# ProPrj___2026-06-05.net
KiCad netlist of a schematic drawn in EasyEDA Pro
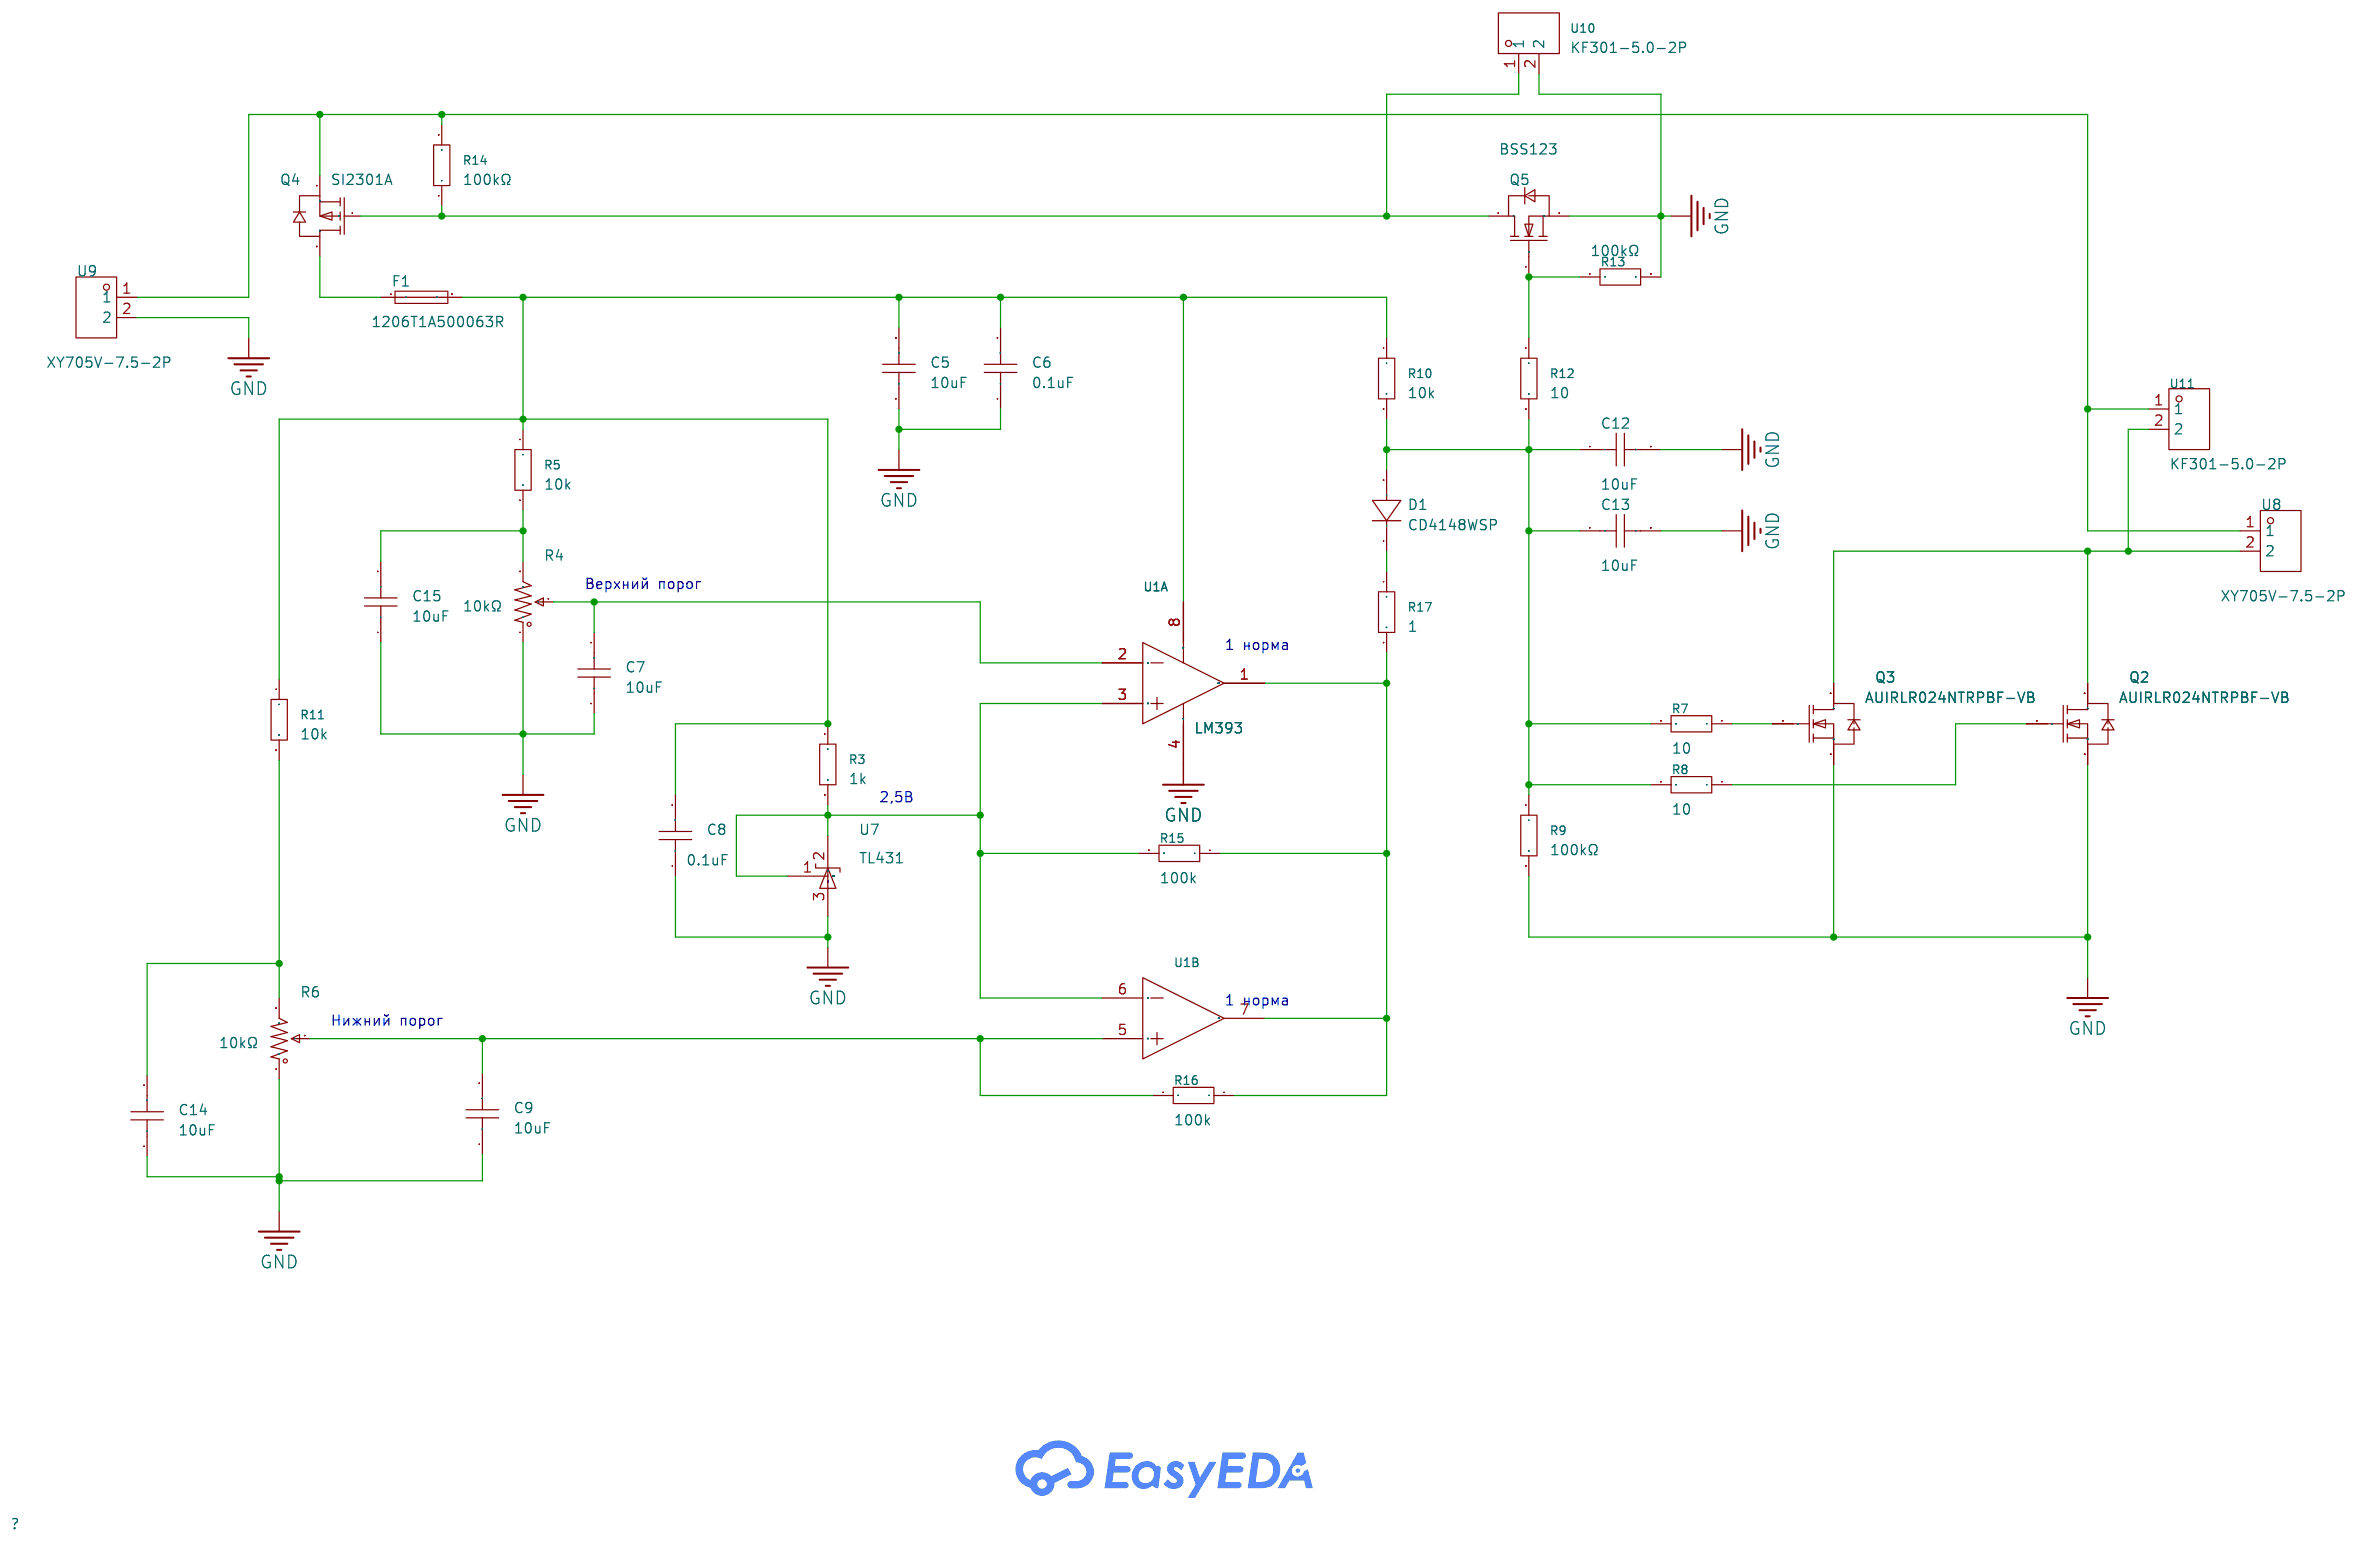
[diagram p0: schematic sheet]

(export (version "E")
  (design (tool "Eeschema 10.0.6"))
  (components
    (comp (ref "C5")
      (value "10uF")
      (footprint "easyedapro:C1206")
      (description "Capacitance:10uF Tolerance:±10% Tolerance:±10% Voltage Rating:50V Temperature Coefficient:X7R")
      (fields (field (name "Manufacturer Part") "1206B106K500NT") (field (name "Manufacturer") "FH(风华)"))
      (libsource (lib "easyedapro") (part "1206B106K500NT"))
    )
    (comp (ref "C6")
      (value "0.1uF")
      (footprint "easyedapro:C1206")
      (description "Capacitance:10uF Tolerance:±10% Tolerance:±10% Voltage Rating:50V Temperature Coefficient:X7R")
      (fields (field (name "Manufacturer Part") "1206B106K500NT") (field (name "Manufacturer") "FH(风华)"))
      (libsource (lib "easyedapro") (part "1206B106K500NT"))
    )
    (comp (ref "C7")
      (value "10uF")
      (footprint "easyedapro:C1206")
      (description "Capacitance:10uF Tolerance:±10% Tolerance:±10% Voltage Rating:50V Temperature Coefficient:X7R")
      (fields (field (name "Manufacturer Part") "1206B106K500NT") (field (name "Manufacturer") "FH(风华)"))
      (libsource (lib "easyedapro") (part "1206B106K500NT"))
    )
    (comp (ref "C8")
      (value "0.1uF")
      (footprint "easyedapro:C1206")
      (description "Capacitance:10uF Tolerance:±10% Tolerance:±10% Voltage Rating:50V Temperature Coefficient:X7R")
      (fields (field (name "Manufacturer Part") "1206B106K500NT") (field (name "Manufacturer") "FH(风华)"))
      (libsource (lib "easyedapro") (part "1206B106K500NT"))
    )
    (comp (ref "C9")
      (value "10uF")
      (footprint "easyedapro:C1206")
      (description "Capacitance:10uF Tolerance:±10% Tolerance:±10% Voltage Rating:50V Temperature Coefficient:X7R")
      (fields (field (name "Manufacturer Part") "1206B106K500NT") (field (name "Manufacturer") "FH(风华)"))
      (libsource (lib "easyedapro") (part "1206B106K500NT"))
    )
    (comp (ref "C12")
      (value "10uF")
      (footprint "easyedapro:C0805")
      (fields (field (name "Manufacturer Part") "C1206X106K025T") (field (name "Manufacturer") "IHHEC(禾伸堂)"))
      (libsource (lib "easyedapro") (part "V106K0805X5R250NHP"))
    )
    (comp (ref "C13")
      (value "10uF")
      (footprint "easyedapro:C0805")
      (fields (field (name "Manufacturer Part") "C1206X106K025T") (field (name "Manufacturer") "IHHEC(禾伸堂)"))
      (libsource (lib "easyedapro") (part "V106K0805X5R250NHP"))
    )
    (comp (ref "C14")
      (value "10uF")
      (footprint "easyedapro:C1206")
      (description "Capacitance:10uF Tolerance:±10% Tolerance:±10% Voltage Rating:50V Temperature Coefficient:X7R")
      (fields (field (name "Manufacturer Part") "1206B106K500NT") (field (name "Manufacturer") "FH(风华)"))
      (libsource (lib "easyedapro") (part "1206B106K500NT"))
    )
    (comp (ref "C15")
      (value "10uF")
      (footprint "easyedapro:C1206")
      (description "Capacitance:10uF Tolerance:±10% Tolerance:±10% Voltage Rating:50V Temperature Coefficient:X7R")
      (fields (field (name "Manufacturer Part") "1206B106K500NT") (field (name "Manufacturer") "FH(风华)"))
      (libsource (lib "easyedapro") (part "1206B106K500NT"))
    )
    (comp (ref "D1")
      (value "CD4148WSP")
      (footprint "easyedapro:D0805-RD")
      (fields (field (name "Manufacturer") "YONGYUTAI(永裕泰)"))
      (libsource (lib "easyedapro") (part "CD4148WSP_C30584799"))
    )
    (comp (ref "F1")
      (value "1206T1A500063R")
      (footprint "easyedapro:F1206")
      (fields (field (name "Manufacturer") "WALTER(华德)"))
      (libsource (lib "easyedapro") (part "1206T1A500063R"))
    )
    (comp (ref "Q2")
      (value "AUIRLR024NTRPBF-VB")
      (footprint "easyedapro:TO-252-2_L6.5-W6.1-P4.56-LS9.9-BR-CW-1")
      (fields (field (name "Manufacturer") "VBsemi(微碧半导体)"))
      (libsource (lib "easyedapro") (part "AUIRLR024NTRPBF-VB"))
    )
    (comp (ref "Q3")
      (value "AUIRLR024NTRPBF-VB")
      (footprint "easyedapro:TO-252-2_L6.5-W6.1-P4.56-LS9.9-BR-CW-1")
      (fields (field (name "Manufacturer") "VBsemi(微碧半导体)"))
      (libsource (lib "easyedapro") (part "AUIRLR024NTRPBF-VB"))
    )
    (comp (ref "Q4")
      (value "SI2301A")
      (footprint "easyedapro:SOT-23-3_L2.9-W1.3-P1.90-LS2.4-BR")
      (fields (field (name "Manufacturer") "YONGYUTAI(永裕泰)"))
      (libsource (lib "easyedapro") (part "SI2301A_C49010227"))
    )
    (comp (ref "Q5")
      (value "BSS123")
      (footprint "easyedapro:SOT-23-3_L3.0-W1.7-P0.95-LS2.9-BR")
      (fields (field (name "Manufacturer") "ElecSuper(静芯)"))
      (libsource (lib "easyedapro") (part "BSS123_C39832210"))
    )
    (comp (ref "R3")
      (value "1k")
      (footprint "easyedapro:R0805")
      (fields (field (name "Manufacturer Part") "RMC0805100K5%N") (field (name "Manufacturer") "Tyohm(幸亚电阻)"))
      (libsource (lib "easyedapro") (part "RMC0805100K5%N"))
    )
    (comp (ref "R4")
      (value "10kΩ")
      (footprint "easyedapro:RES-ADJ-TH_3P-L10.0-W10.0-P2.50-L")
      (fields (field (name "Manufacturer Part") "3296W-1-103") (field (name "Manufacturer") "BOCHEN(博晨)"))
      (libsource (lib "easyedapro") (part "3296W-1-103"))
    )
    (comp (ref "R5")
      (value "10k")
      (footprint "easyedapro:R0805")
      (fields (field (name "Manufacturer Part") "RMC0805100K5%N") (field (name "Manufacturer") "Tyohm(幸亚电阻)"))
      (libsource (lib "easyedapro") (part "RMC0805100K5%N"))
    )
    (comp (ref "R6")
      (value "10kΩ")
      (footprint "easyedapro:RES-ADJ-TH_3P-L10.0-W10.0-P2.50-L")
      (fields (field (name "Manufacturer Part") "3296W-1-103") (field (name "Manufacturer") "BOCHEN(博晨)"))
      (libsource (lib "easyedapro") (part "3296W-1-103"))
    )
    (comp (ref "R7")
      (value "10")
      (footprint "easyedapro:R0805")
      (fields (field (name "Manufacturer Part") "RMC0805100K5%N") (field (name "Manufacturer") "Tyohm(幸亚电阻)"))
      (libsource (lib "easyedapro") (part "RMC0805100K5%N"))
    )
    (comp (ref "R8")
      (value "10")
      (footprint "easyedapro:R0805")
      (fields (field (name "Manufacturer Part") "RMC0805100K5%N") (field (name "Manufacturer") "Tyohm(幸亚电阻)"))
      (libsource (lib "easyedapro") (part "RMC0805100K5%N"))
    )
    (comp (ref "R9")
      (value "100kΩ")
      (footprint "easyedapro:R0805")
      (fields (field (name "Manufacturer Part") "RMC0805100K5%N") (field (name "Manufacturer") "Tyohm(幸亚电阻)"))
      (libsource (lib "easyedapro") (part "RMC0805100K5%N"))
    )
    (comp (ref "R10")
      (value "10k")
      (footprint "easyedapro:R0805")
      (fields (field (name "Manufacturer Part") "RMC0805100K5%N") (field (name "Manufacturer") "Tyohm(幸亚电阻)"))
      (libsource (lib "easyedapro") (part "RMC0805100K5%N"))
    )
    (comp (ref "R11")
      (value "10k")
      (footprint "easyedapro:R0805")
      (fields (field (name "Manufacturer Part") "RMC0805100K5%N") (field (name "Manufacturer") "Tyohm(幸亚电阻)"))
      (libsource (lib "easyedapro") (part "RMC0805100K5%N"))
    )
    (comp (ref "R12")
      (value "10")
      (footprint "easyedapro:R0805")
      (fields (field (name "Manufacturer Part") "RMC0805100K5%N") (field (name "Manufacturer") "Tyohm(幸亚电阻)"))
      (libsource (lib "easyedapro") (part "RMC0805100K5%N"))
    )
    (comp (ref "R13")
      (value "100kΩ")
      (footprint "easyedapro:R0805")
      (fields (field (name "Manufacturer Part") "RMC0805100K5%N") (field (name "Manufacturer") "Tyohm(幸亚电阻)"))
      (libsource (lib "easyedapro") (part "RMC0805100K5%N"))
    )
    (comp (ref "R14")
      (value "100kΩ")
      (footprint "easyedapro:R0805")
      (fields (field (name "Manufacturer Part") "RMC0805100K5%N") (field (name "Manufacturer") "Tyohm(幸亚电阻)"))
      (libsource (lib "easyedapro") (part "RMC0805100K5%N"))
    )
    (comp (ref "R15")
      (value "100k")
      (footprint "easyedapro:R0805")
      (fields (field (name "Manufacturer Part") "RMC0805100K5%N") (field (name "Manufacturer") "Tyohm(幸亚电阻)"))
      (libsource (lib "easyedapro") (part "RMC0805100K5%N"))
    )
    (comp (ref "R16")
      (value "100k")
      (footprint "easyedapro:R0805")
      (fields (field (name "Manufacturer Part") "RMC0805100K5%N") (field (name "Manufacturer") "Tyohm(幸亚电阻)"))
      (libsource (lib "easyedapro") (part "RMC0805100K5%N"))
    )
    (comp (ref "R17")
      (value "1")
      (footprint "easyedapro:R0805")
      (fields (field (name "Manufacturer Part") "RMC0805100K5%N") (field (name "Manufacturer") "Tyohm(幸亚电阻)"))
      (libsource (lib "easyedapro") (part "RMC0805100K5%N"))
    )
    (comp (ref "U1")
      (value "LM393")
      (footprint "easyedapro:SOP-8_L4.9-W3.9-P1.27-LS6.0-BL")
      (fields (field (name "Manufacturer") "MSKSEMI(美森科)"))
      (libsource (lib "easyedapro") (part "LM393_C5252905"))
    )
    (comp (ref "U7")
      (value "TL431")
      (footprint "easyedapro:SOT-23-3_L2.9-W1.3-P0.95-LS2.4-BR")
      (fields (field (name "Manufacturer") "KUU"))
      (libsource (lib "easyedapro") (part "TL431_C49195703"))
    )
    (comp (ref "U8")
      (value "XY705V-7.5-2P")
      (footprint "easyedapro:CONN-TH_XY705V-7.5-2P")
      (fields (field (name "Manufacturer") "XINLAIYA(新莱亚)"))
      (libsource (lib "easyedapro") (part "XY705V-7.5-2P"))
    )
    (comp (ref "U9")
      (value "XY705V-7.5-2P")
      (footprint "easyedapro:CONN-TH_XY705V-7.5-2P")
      (fields (field (name "Manufacturer") "XINLAIYA(新莱亚)"))
      (libsource (lib "easyedapro") (part "XY705V-7.5-2P"))
    )
    (comp (ref "U10")
      (value "KF301-5.0-2P")
      (footprint "easyedapro:CONN-TH_P5.00_KF301-5.0-2P")
      (fields (field (name "Manufacturer") "KEFA(科发)"))
      (libsource (lib "easyedapro") (part "KF301-5.0-2P"))
    )
    (comp (ref "U11")
      (value "KF301-5.0-2P")
      (footprint "easyedapro:CONN-TH_P5.00_KF301-5.0-2P")
      (fields (field (name "Manufacturer") "KEFA(科发)"))
      (libsource (lib "easyedapro") (part "KF301-5.0-2P"))
    )
  )
  (nets
    (net (code "1") (name "GND") (class "Default")
      (node (ref "C12") (pin "2") (pinfunction "2_2") (pintype "unspecified"))
      (node (ref "C13") (pin "2") (pinfunction "2_2") (pintype "unspecified"))
      (node (ref "C14") (pin "1") (pinfunction "1_1") (pintype "unspecified"))
      (node (ref "C15") (pin "1") (pinfunction "1_1") (pintype "unspecified"))
      (node (ref "C5") (pin "1") (pinfunction "1_1") (pintype "unspecified"))
      (node (ref "C6") (pin "1") (pinfunction "1_1") (pintype "unspecified"))
      (node (ref "C7") (pin "1") (pinfunction "1_1") (pintype "unspecified"))
      (node (ref "C8") (pin "1") (pinfunction "1_1") (pintype "unspecified"))
      (node (ref "C9") (pin "1") (pinfunction "1_1") (pintype "unspecified"))
      (node (ref "Q2") (pin "3") (pinfunction "S_3") (pintype "unspecified"))
      (node (ref "Q3") (pin "3") (pinfunction "S_3") (pintype "unspecified"))
      (node (ref "Q5") (pin "2") (pinfunction "S_2") (pintype "unspecified"))
      (node (ref "R13") (pin "2") (pinfunction "2_2") (pintype "input"))
      (node (ref "R4") (pin "1") (pinfunction "1_1") (pintype "input"))
      (node (ref "R6") (pin "1") (pinfunction "1_1") (pintype "input"))
      (node (ref "R9") (pin "2") (pinfunction "2_2") (pintype "input"))
      (node (ref "U1") (pin "4") (pinfunction "VEE_4") (pintype "input"))
      (node (ref "U10") (pin "2") (pinfunction "2_2") (pintype "input"))
      (node (ref "U7") (pin "3") (pinfunction "ANODE_3") (pintype "unspecified"))
      (node (ref "U9") (pin "2") (pinfunction "2_2") (pintype "unspecified"))
    )
    (net (code "2") (name "Net-(C14-Pad2)") (class "Default")
      (node (ref "C14") (pin "2") (pinfunction "2_2") (pintype "unspecified"))
      (node (ref "R11") (pin "2") (pinfunction "2_2") (pintype "input"))
      (node (ref "R6") (pin "3") (pinfunction "3_3") (pintype "input"))
    )
    (net (code "3") (name "Net-(C15-Pad2)") (class "Default")
      (node (ref "C15") (pin "2") (pinfunction "2_2") (pintype "unspecified"))
      (node (ref "R4") (pin "3") (pinfunction "3_3") (pintype "input"))
      (node (ref "R5") (pin "2") (pinfunction "2_2") (pintype "input"))
    )
    (net (code "4") (name "Net-(D1-A)") (class "Default")
      (node (ref "C12") (pin "1") (pinfunction "1_1") (pintype "unspecified"))
      (node (ref "C13") (pin "1") (pinfunction "1_1") (pintype "unspecified"))
      (node (ref "D1") (pin "2") (pinfunction "A_2") (pintype "unspecified"))
      (node (ref "R10") (pin "2") (pinfunction "2_2") (pintype "input"))
      (node (ref "R12") (pin "2") (pinfunction "2_2") (pintype "input"))
      (node (ref "R7") (pin "2") (pinfunction "2_2") (pintype "input"))
      (node (ref "R8") (pin "2") (pinfunction "2_2") (pintype "input"))
      (node (ref "R9") (pin "1") (pinfunction "1_1") (pintype "input"))
    )
    (net (code "5") (name "Net-(D1-K)") (class "Default")
      (node (ref "D1") (pin "1") (pinfunction "K_1") (pintype "unspecified"))
      (node (ref "R17") (pin "1") (pinfunction "1_1") (pintype "input"))
    )
    (net (code "6") (name "Net-(Q2-D)") (class "Default")
      (node (ref "Q2") (pin "2") (pinfunction "D_2") (pintype "unspecified"))
      (node (ref "Q3") (pin "2") (pinfunction "D_2") (pintype "unspecified"))
      (node (ref "U11") (pin "2") (pinfunction "2_2") (pintype "input"))
      (node (ref "U8") (pin "2") (pinfunction "2_2") (pintype "unspecified"))
    )
    (net (code "7") (name "Net-(Q2-G)") (class "Default")
      (node (ref "Q2") (pin "1") (pinfunction "G_1") (pintype "unspecified"))
      (node (ref "R8") (pin "1") (pinfunction "1_1") (pintype "input"))
    )
    (net (code "8") (name "Net-(Q3-G)") (class "Default")
      (node (ref "Q3") (pin "1") (pinfunction "G_1") (pintype "unspecified"))
      (node (ref "R7") (pin "1") (pinfunction "1_1") (pintype "input"))
    )
    (net (code "9") (name "Net-(Q4-D)") (class "Default")
      (node (ref "F1") (pin "1") (pinfunction "1_1") (pintype "unspecified"))
      (node (ref "Q4") (pin "3") (pinfunction "D_3") (pintype "unspecified"))
    )
    (net (code "10") (name "Net-(Q4-G)") (class "Default")
      (node (ref "Q4") (pin "1") (pinfunction "G_1") (pintype "unspecified"))
      (node (ref "Q5") (pin "3") (pinfunction "D_3") (pintype "unspecified"))
      (node (ref "R14") (pin "1") (pinfunction "1_1") (pintype "input"))
      (node (ref "U10") (pin "1") (pinfunction "1_1") (pintype "input"))
    )
    (net (code "11") (name "Net-(Q4-S)") (class "Default")
      (node (ref "Q4") (pin "2") (pinfunction "S_2") (pintype "unspecified"))
      (node (ref "R14") (pin "2") (pinfunction "2_2") (pintype "input"))
      (node (ref "U11") (pin "1") (pinfunction "1_1") (pintype "input"))
      (node (ref "U8") (pin "1") (pinfunction "1_1") (pintype "unspecified"))
      (node (ref "U9") (pin "1") (pinfunction "1_1") (pintype "unspecified"))
    )
    (net (code "12") (name "Net-(Q5-G)") (class "Default")
      (node (ref "Q5") (pin "1") (pinfunction "G_1") (pintype "unspecified"))
      (node (ref "R12") (pin "1") (pinfunction "1_1") (pintype "input"))
      (node (ref "R13") (pin "1") (pinfunction "1_1") (pintype "input"))
    )
    (net (code "13") (name "Net-(U1A-1IN+)") (class "Default")
      (node (ref "R15") (pin "2") (pinfunction "2_2") (pintype "input"))
      (node (ref "R3") (pin "2") (pinfunction "2_2") (pintype "input"))
      (node (ref "U1") (pin "3") (pinfunction "1IN+_3") (pintype "input"))
      (node (ref "U1") (pin "6") (pinfunction "2IN-_6") (pintype "input"))
      (node (ref "U7") (pin "1") (pinfunction "REFERENCE_1") (pintype "unspecified"))
      (node (ref "U7") (pin "2") (pinfunction "CATHODE_2") (pintype "unspecified"))
    )
    (net (code "14") (name "Net-(U1A-1IN-)") (class "Default")
      (node (ref "C7") (pin "2") (pinfunction "2_2") (pintype "unspecified"))
      (node (ref "R4") (pin "2") (pinfunction "2_2") (pintype "input"))
      (node (ref "U1") (pin "2") (pinfunction "1IN-_2") (pintype "input"))
    )
    (net (code "15") (name "Net-(U1A-1OUT1)") (class "Default")
      (node (ref "R15") (pin "1") (pinfunction "1_1") (pintype "input"))
      (node (ref "R16") (pin "1") (pinfunction "1_1") (pintype "input"))
      (node (ref "R17") (pin "2") (pinfunction "2_2") (pintype "input"))
      (node (ref "U1") (pin "1") (pinfunction "1OUT1_1") (pintype "output"))
      (node (ref "U1") (pin "7") (pinfunction "2OUT_7") (pintype "output"))
    )
    (net (code "16") (name "Net-(U1A-VCC)") (class "Default")
      (node (ref "C5") (pin "2") (pinfunction "2_2") (pintype "unspecified"))
      (node (ref "C6") (pin "2") (pinfunction "2_2") (pintype "unspecified"))
      (node (ref "C8") (pin "2") (pinfunction "2_2") (pintype "unspecified"))
      (node (ref "F1") (pin "2") (pinfunction "2_2") (pintype "unspecified"))
      (node (ref "R10") (pin "1") (pinfunction "1_1") (pintype "input"))
      (node (ref "R11") (pin "1") (pinfunction "1_1") (pintype "input"))
      (node (ref "R3") (pin "1") (pinfunction "1_1") (pintype "input"))
      (node (ref "R5") (pin "1") (pinfunction "1_1") (pintype "input"))
      (node (ref "U1") (pin "8") (pinfunction "VCC_8") (pintype "input"))
    )
    (net (code "17") (name "Net-(U1B-2IN+)") (class "Default")
      (node (ref "C9") (pin "2") (pinfunction "2_2") (pintype "unspecified"))
      (node (ref "R16") (pin "2") (pinfunction "2_2") (pintype "input"))
      (node (ref "R6") (pin "2") (pinfunction "2_2") (pintype "input"))
      (node (ref "U1") (pin "5") (pinfunction "2IN+_5") (pintype "input"))
    )
  )
)
